# 2_Microcontroler_48.net
KiCad netlist of a schematic drawn in Altium Designer
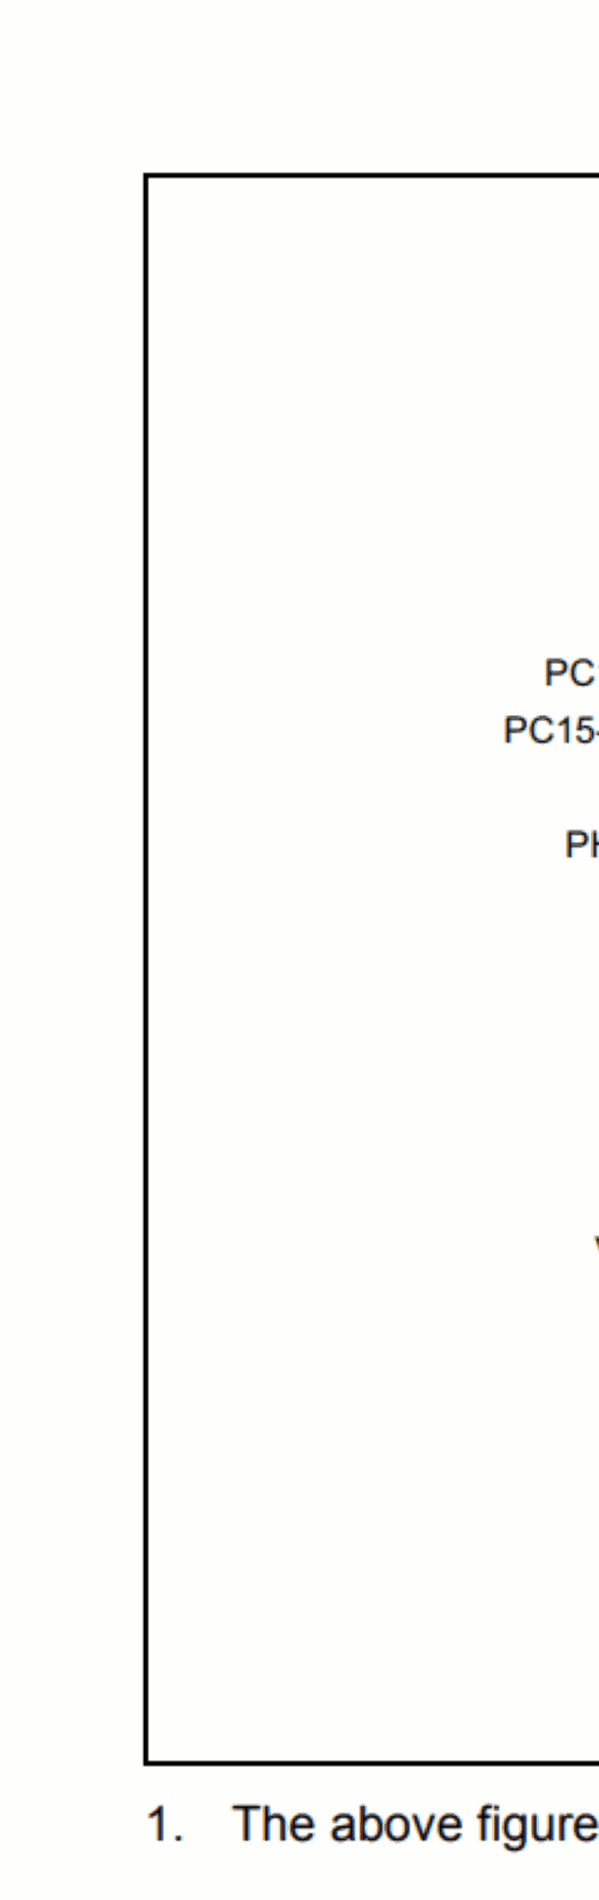
[diagram p0: 2_Microcontroler_48.SchDoc, top left]
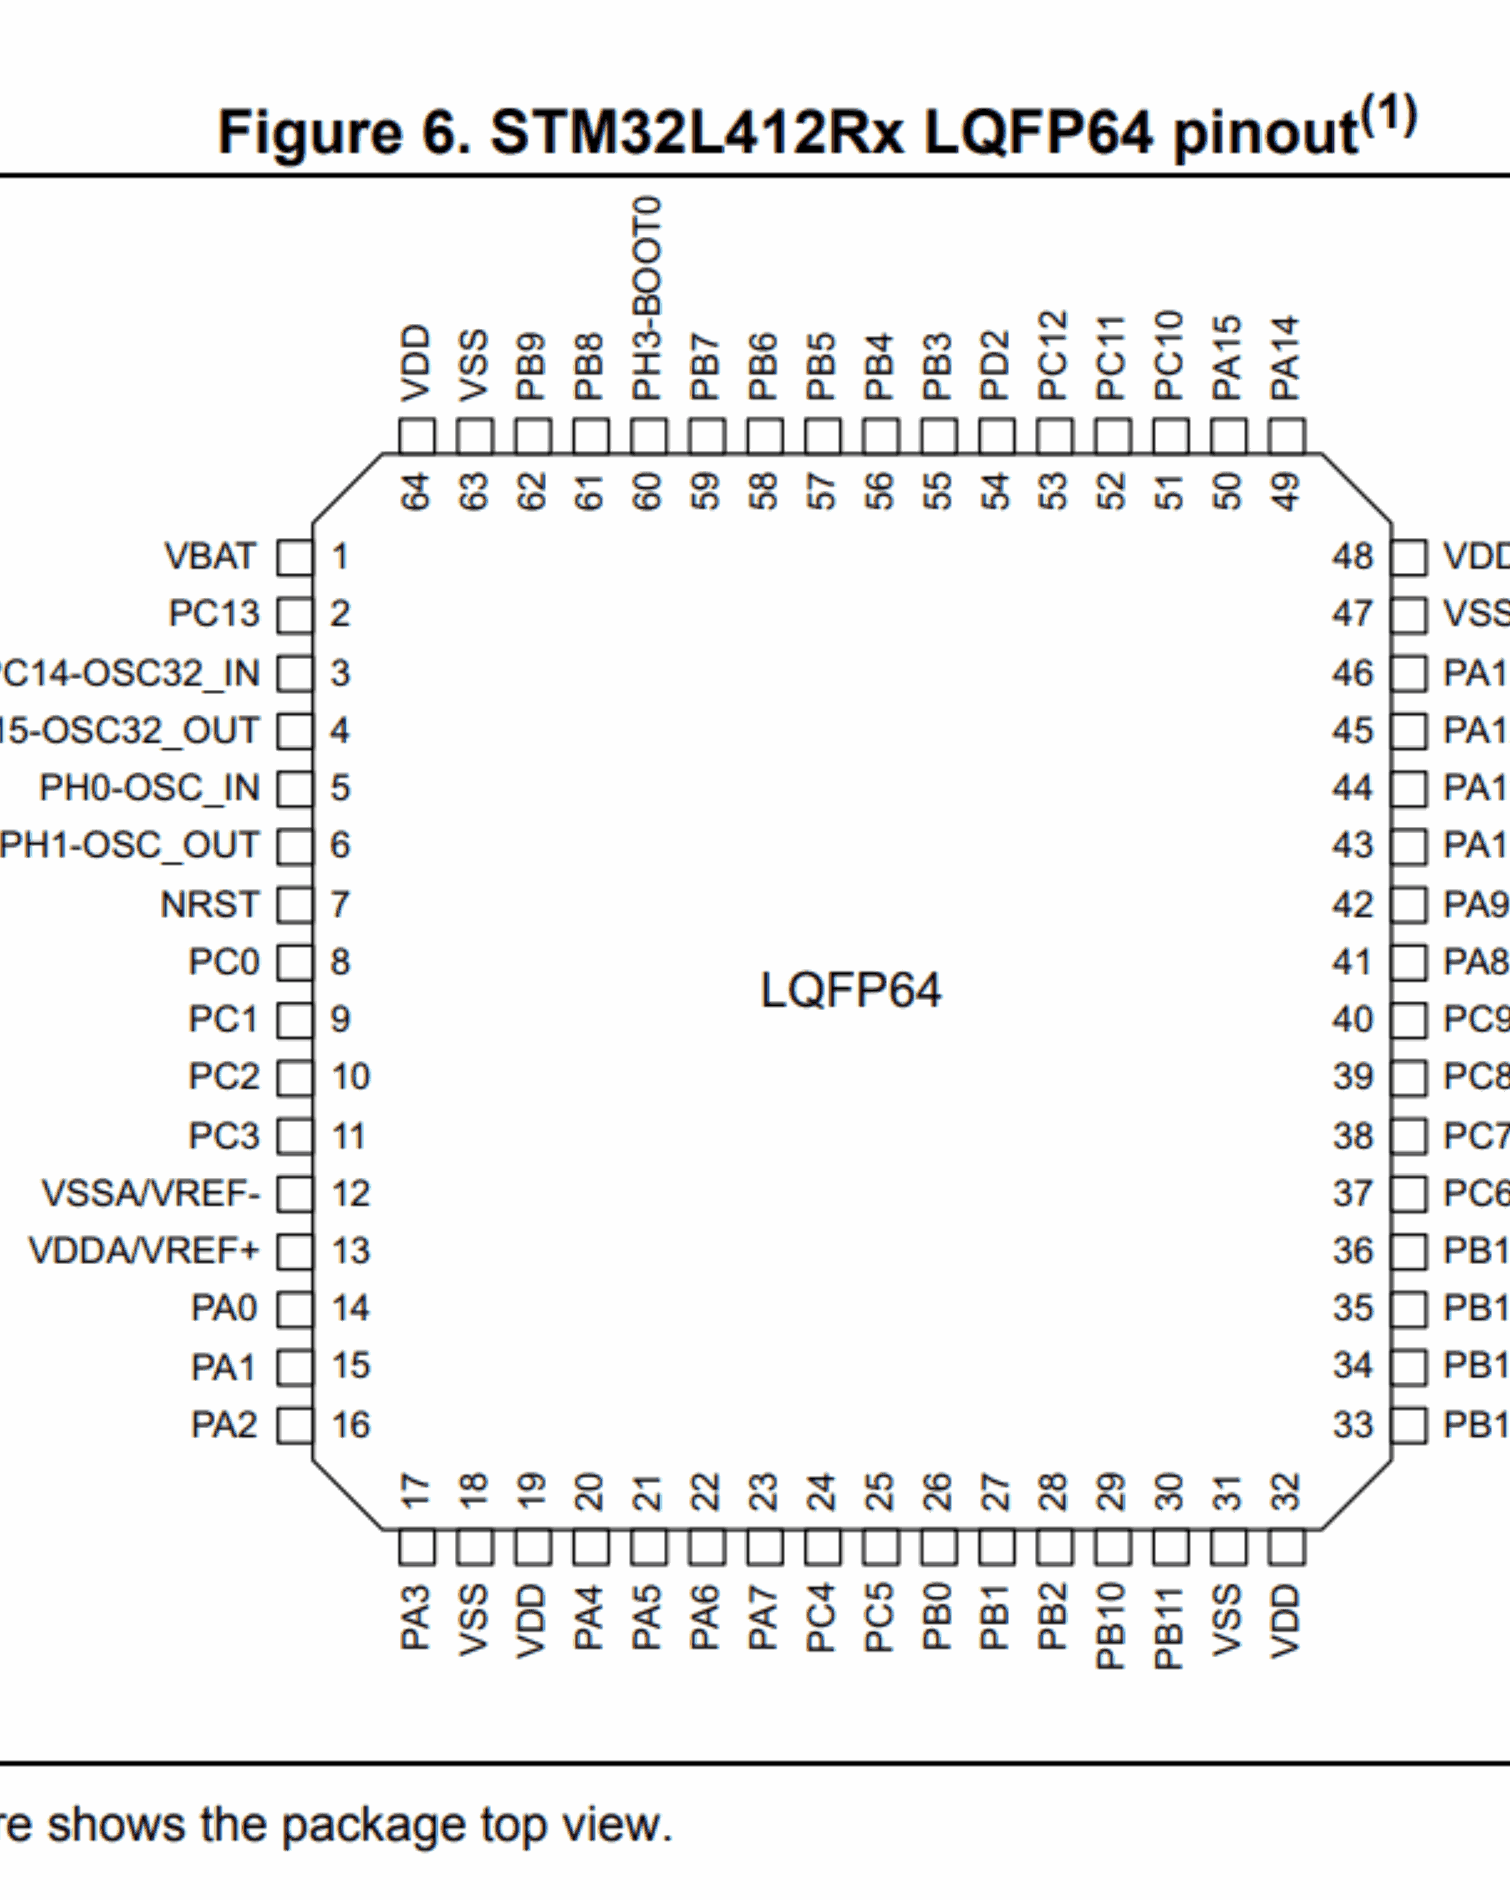
[diagram p1: 2_Microcontroler_48.SchDoc, top middle]
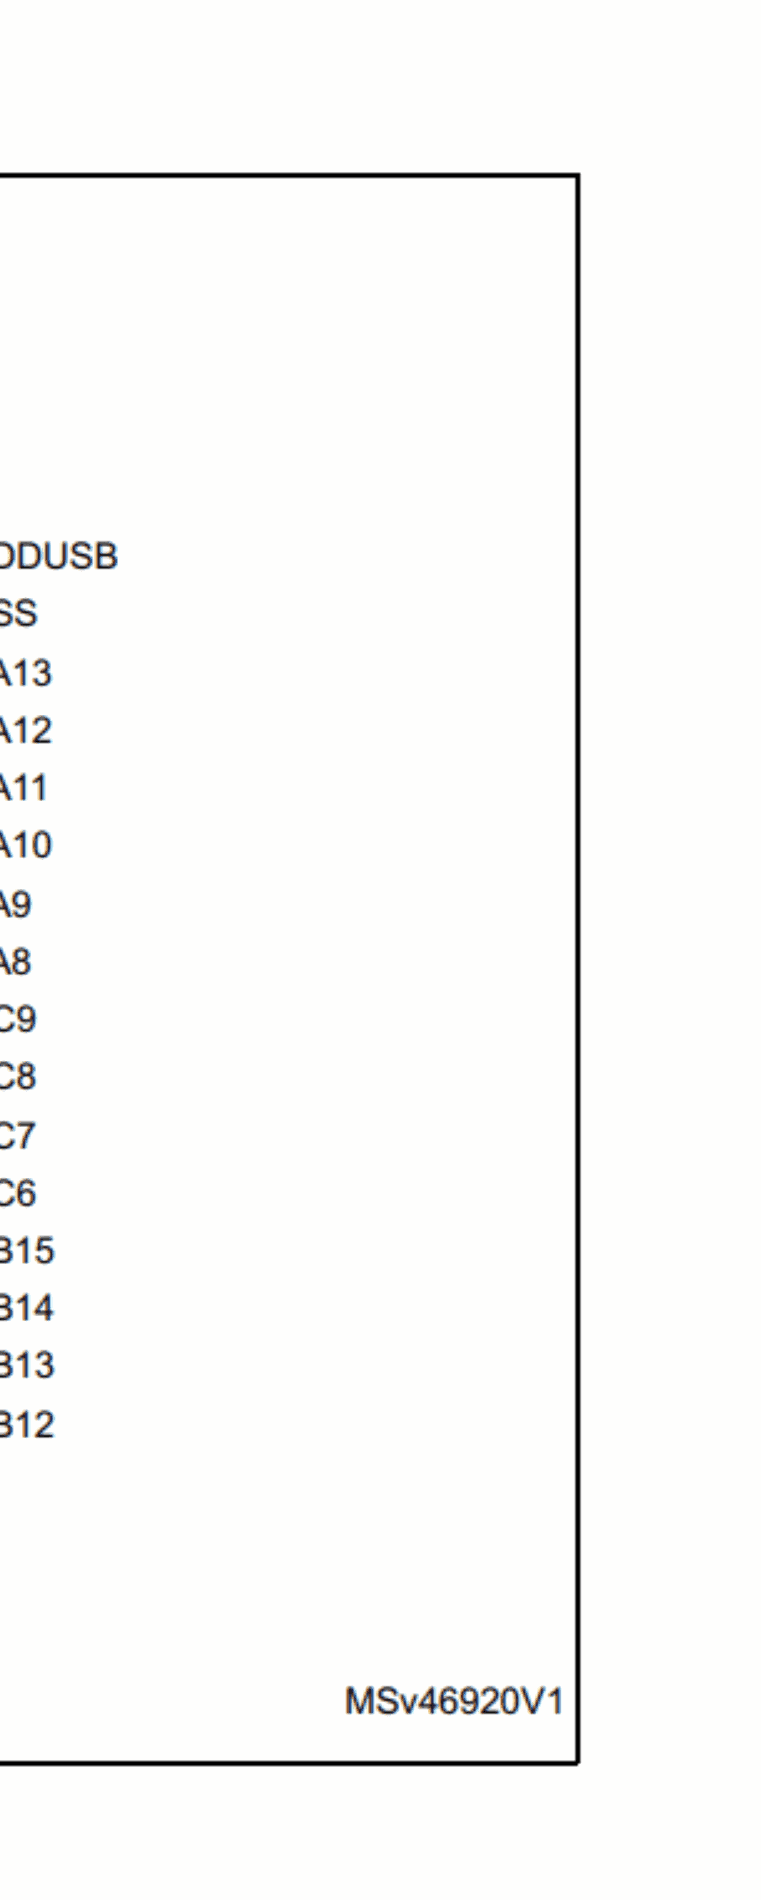
[diagram p2: 2_Microcontroler_48.SchDoc, top right]
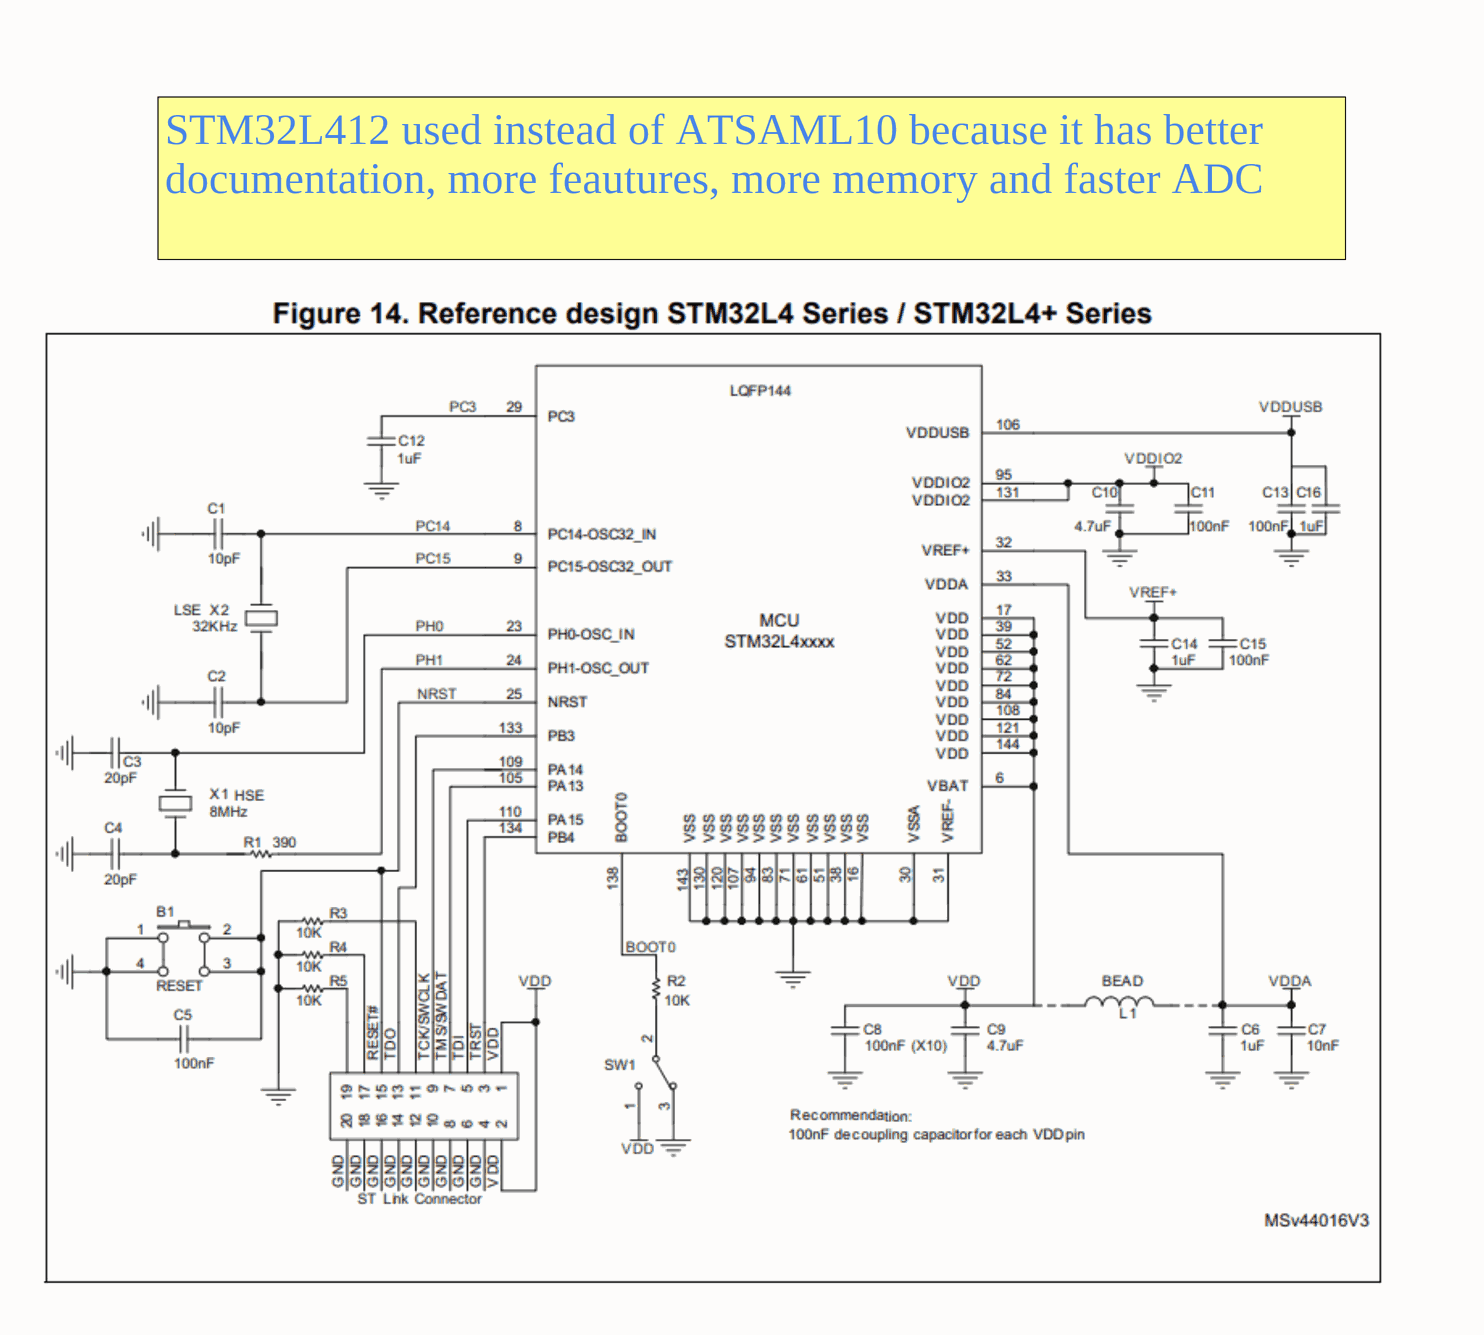
[diagram p3: 2_Microcontroler_48.SchDoc, bottom left]
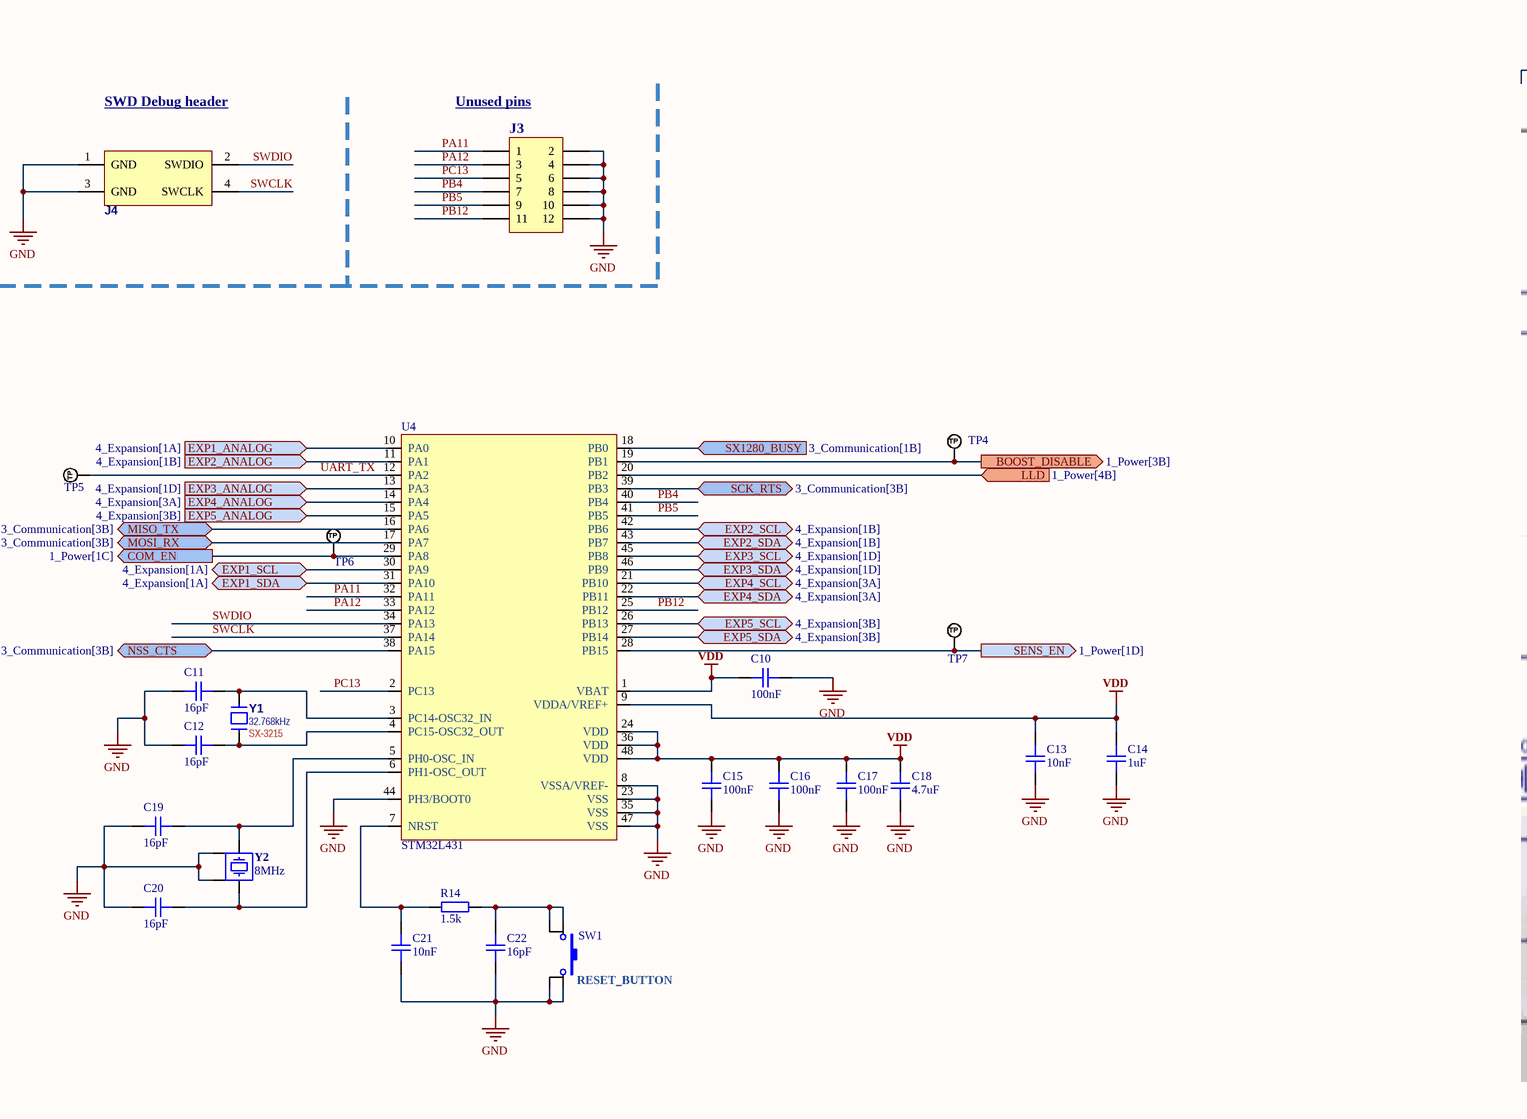
[diagram p4: 2_Microcontroler_48.SchDoc, bottom middle]
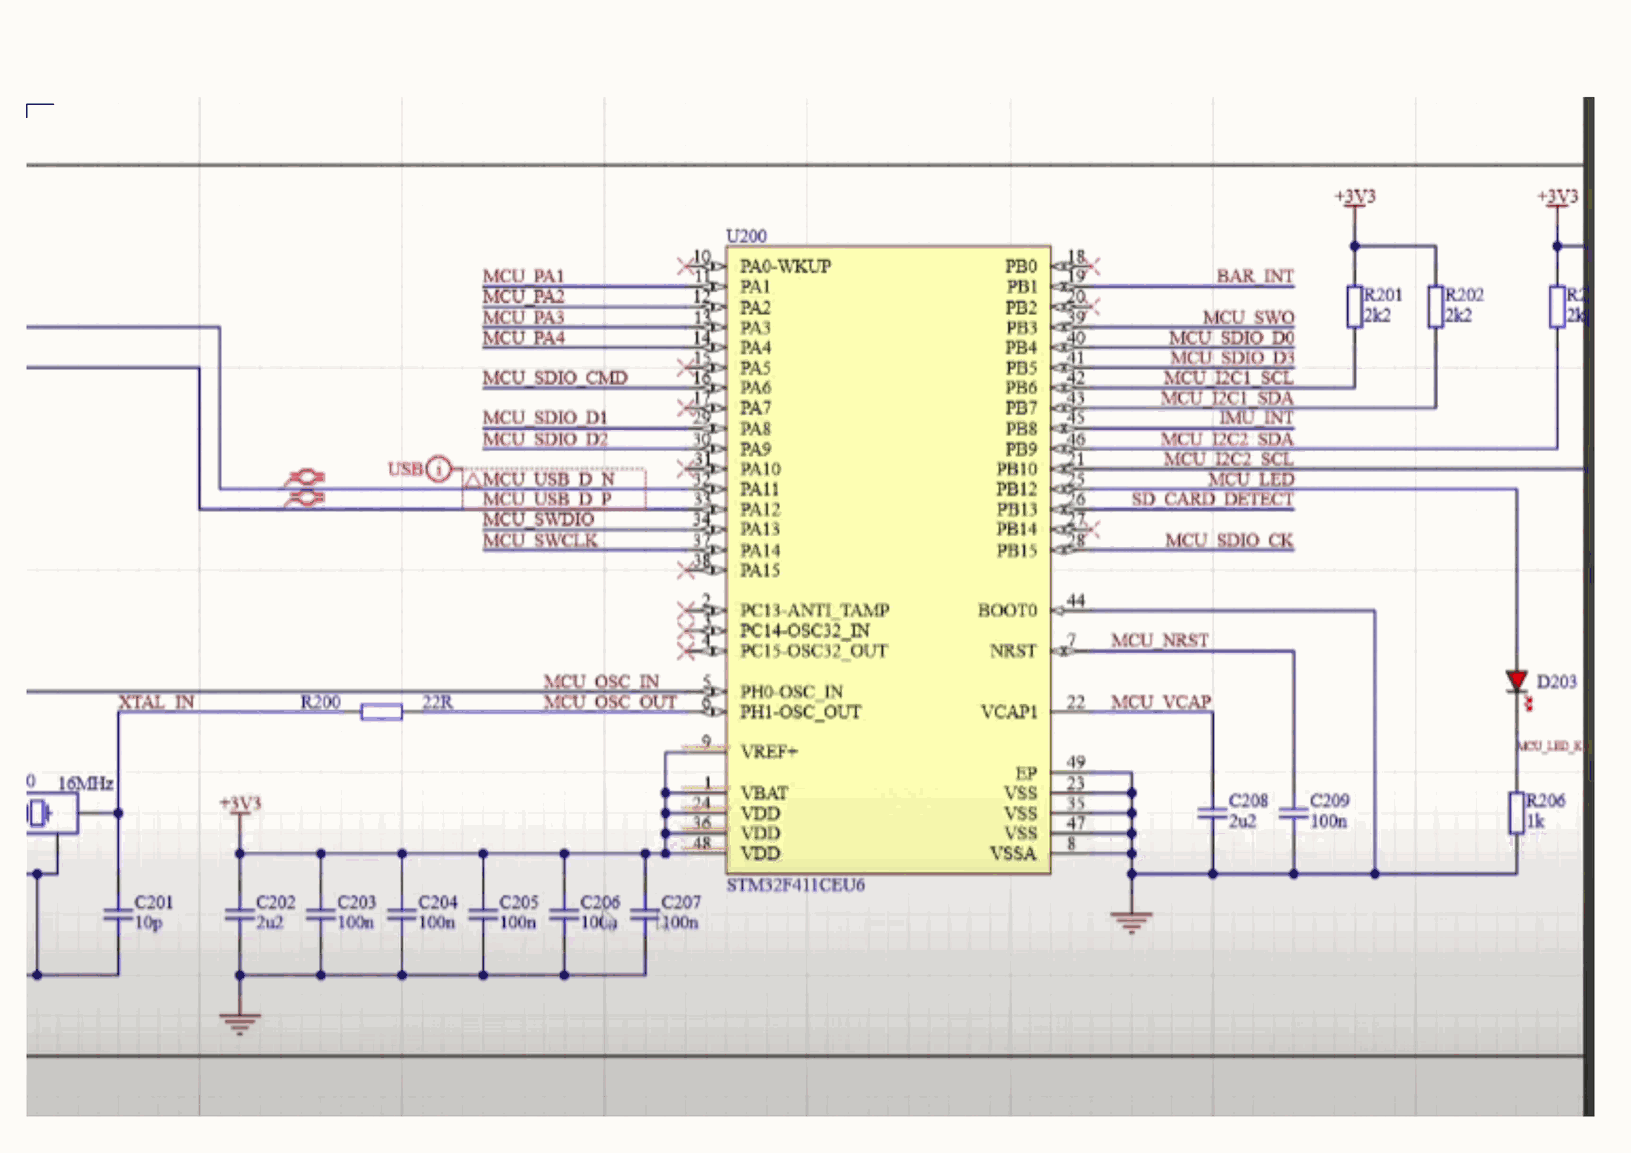
[diagram p5: 2_Microcontroler_48.SchDoc, bottom right]

(export (version "E")
  (design (tool "Eeschema 10.0.6"))
  (components
    (comp (ref "C10")
      (value "100nF")
      (footprint "C0603")
      (description "Capacitor SMD 0603")
      (libsource (lib "Schlib_H2") (part "CAP_0603"))
    )
    (comp (ref "C11")
      (value "16pF")
      (footprint "C0603")
      (description "Capacitor SMD 0603")
      (libsource (lib "Schlib_H2") (part "CAP_0603"))
    )
    (comp (ref "C12")
      (value "16pF")
      (footprint "C0603")
      (description "Capacitor SMD 0603")
      (libsource (lib "Schlib_H2") (part "CAP_0603"))
    )
    (comp (ref "C13")
      (value "10nF")
      (footprint "C0603")
      (description "Capacitor SMD 0603")
      (libsource (lib "Schlib_H2") (part "CAP_0603"))
    )
    (comp (ref "C14")
      (value "1uF")
      (footprint "C0603")
      (description "Capacitor SMD 0603")
      (libsource (lib "Schlib_H2") (part "CAP_0603"))
    )
    (comp (ref "C15")
      (value "100nF")
      (footprint "C0603")
      (description "Capacitor SMD 0603")
      (libsource (lib "Schlib_H2") (part "CAP_0603"))
    )
    (comp (ref "C16")
      (value "100nF")
      (footprint "C0603")
      (description "Capacitor SMD 0603")
      (libsource (lib "Schlib_H2") (part "CAP_0603"))
    )
    (comp (ref "C17")
      (value "100nF")
      (footprint "C0603")
      (description "Capacitor SMD 0603")
      (libsource (lib "Schlib_H2") (part "CAP_0603"))
    )
    (comp (ref "C18")
      (value "4.7uF")
      (footprint "C0603")
      (description "Capacitor SMD 0603")
      (libsource (lib "Schlib_H2") (part "CAP_0603"))
    )
    (comp (ref "C19")
      (value "16pF")
      (footprint "C0603")
      (description "Capacitor SMD 0603")
      (libsource (lib "Schlib_H2") (part "CAP_0603"))
    )
    (comp (ref "C20")
      (value "16pF")
      (footprint "C0603")
      (description "Capacitor SMD 0603")
      (libsource (lib "Schlib_H2") (part "CAP_0603"))
    )
    (comp (ref "C21")
      (value "10nF")
      (footprint "C0603")
      (description "Capacitor SMD 0603")
      (libsource (lib "Schlib_H2") (part "CAP_0603"))
    )
    (comp (ref "C22")
      (value "16pF")
      (footprint "C0603")
      (description "Capacitor SMD 0603")
      (libsource (lib "Schlib_H2") (part "CAP_0603"))
    )
    (comp (ref "J3")
      (value "Header 6X2")
      (footprint "HEADER_6x2_2.54")
      (description "Header, 12-Pin, Dual row")
      (fields (field (name "PUBLISHER") "Altium Limited"))
      (libsource (lib "Schlib_H2") (part "Header 6x2"))
    )
    (comp (ref "J4")
      (value "SWD connector")
      (footprint "HEADER_2x2_2.54")
      (description "Single Wire Debug connector with UART _TX pin")
      (libsource (lib "Schlib_H2") (part "SWD connector"))
    )
    (comp (ref "R14")
      (value "1.5k")
      (footprint "R0603")
      (description "Resistor SMD 0603")
      (libsource (lib "Schlib_H2") (part "RES_0603"))
    )
    (comp (ref "SW1")
      (value "PTS645SM43SMTR92 LFS")
      (footprint "SW_SKRPACE010")
      (description "Switch")
      (fields (field (name "PUBLISHER") "Altium Limited"))
      (libsource (lib "Schlib_H2") (part "SW-PB"))
    )
    (comp (ref "TP4")
      (value "TP_NOBOM")
      (footprint "TEST_PAD_THD")
      (description "Test Point Round 1mm (NO BOM)")
      (libsource (lib "Schlib_H2") (part "TEST_POINT_RND_1MM"))
    )
    (comp (ref "TP5")
      (value "TP_NOBOM")
      (footprint "TEST_PAD_THD")
      (description "Test Point Round 1mm (NO BOM)")
      (libsource (lib "Schlib_H2") (part "TEST_POINT_RND_1MM"))
    )
    (comp (ref "TP6")
      (value "TP_NOBOM")
      (footprint "TEST_PAD_THD")
      (description "Test Point Round 1mm (NO BOM)")
      (libsource (lib "Schlib_H2") (part "TEST_POINT_RND_1MM"))
    )
    (comp (ref "TP7")
      (value "TP_NOBOM")
      (footprint "TEST_PAD_THD")
      (description "Test Point Round 1mm (NO BOM)")
      (libsource (lib "Schlib_H2") (part "TEST_POINT_RND_1MM"))
    )
    (comp (ref "U4")
      (value "STM32L431")
      (footprint "QFPN-48")
      (description "Ultra-low-power Arm® Cortex®-M4 32-bit MCU+FPU, 100DMIPS,\r\n up to 128KB flash, 40KB SRAM(LQFP48)")
      (libsource (lib "Schlib_H2") (part "STM32L431"))
    )
    (comp (ref "Y1")
      (value "32.768kHz")
      (footprint "CRYSTAL_SX-3215")
      (description "Crystal")
      (fields (field (name "PACKAGEREFERENCE") "SX-3215"))
      (libsource (lib "Schlib_H2") (part "CRYSTAL_1"))
    )
    (comp (ref "Y2")
      (value "8MHz")
      (footprint "CRYSTAL_ECX-32_3.2x2.5x0.8 - duplicate")
      (description "Crystal")
      (fields
        (field (name "MANUFACTURER") "Epson")
        (field (name "MANUFACTURER PART NUMBER") "TSX-3225 24.0000MF15X-AC")
      )
      (libsource (lib "Schlib_H2") (part "Crystal"))
    )
  )
  (nets
    (net (code "1") (name "/BOOST_DISABLE") (class "Default")
      (node (ref "TP4") (pin "1") (pinfunction "TP_1") (pintype "passive"))
      (node (ref "U4") (pin "19") (pinfunction "PB1_19") (pintype "passive"))
    )
    (net (code "2") (name "/COM_EN") (class "Default")
      (node (ref "TP6") (pin "1") (pinfunction "TP_1") (pintype "passive"))
      (node (ref "U4") (pin "29") (pinfunction "PA8_29") (pintype "passive"))
    )
    (net (code "3") (name "/EXP1_ANALOG") (class "Default")
      (node (ref "U4") (pin "10") (pinfunction "PA0_10") (pintype "passive"))
    )
    (net (code "4") (name "/EXP1_SCL") (class "Default")
      (node (ref "U4") (pin "30") (pinfunction "PA9_30") (pintype "passive"))
    )
    (net (code "5") (name "/EXP1_SDA") (class "Default")
      (node (ref "U4") (pin "31") (pinfunction "PA10_31") (pintype "passive"))
    )
    (net (code "6") (name "/EXP2_ANALOG") (class "Default")
      (node (ref "U4") (pin "11") (pinfunction "PA1_11") (pintype "passive"))
    )
    (net (code "7") (name "/EXP2_SCL") (class "Default")
      (node (ref "U4") (pin "42") (pinfunction "PB6_42") (pintype "passive"))
    )
    (net (code "8") (name "/EXP2_SDA") (class "Default")
      (node (ref "U4") (pin "43") (pinfunction "PB7_43") (pintype "passive"))
    )
    (net (code "9") (name "/EXP3_ANALOG") (class "Default")
      (node (ref "U4") (pin "13") (pinfunction "PA3_13") (pintype "passive"))
    )
    (net (code "10") (name "/EXP3_SCL") (class "Default")
      (node (ref "U4") (pin "45") (pinfunction "PB8_45") (pintype "passive"))
    )
    (net (code "11") (name "/EXP3_SDA") (class "Default")
      (node (ref "U4") (pin "46") (pinfunction "PB9_46") (pintype "passive"))
    )
    (net (code "12") (name "/EXP4_ANALOG") (class "Default")
      (node (ref "U4") (pin "14") (pinfunction "PA4_14") (pintype "passive"))
    )
    (net (code "13") (name "/EXP4_SCL") (class "Default")
      (node (ref "U4") (pin "21") (pinfunction "PB10_21") (pintype "passive"))
    )
    (net (code "14") (name "/EXP4_SDA") (class "Default")
      (node (ref "U4") (pin "22") (pinfunction "PB11_22") (pintype "passive"))
    )
    (net (code "15") (name "/EXP5_ANALOG") (class "Default")
      (node (ref "U4") (pin "15") (pinfunction "PA5_15") (pintype "passive"))
    )
    (net (code "16") (name "/EXP5_SCL") (class "Default")
      (node (ref "U4") (pin "26") (pinfunction "PB13_26") (pintype "passive"))
    )
    (net (code "17") (name "/EXP5_SDA") (class "Default")
      (node (ref "U4") (pin "27") (pinfunction "PB14_27") (pintype "passive"))
    )
    (net (code "18") (name "/LLD") (class "Default")
      (node (ref "U4") (pin "20") (pinfunction "PB2_20") (pintype "passive"))
    )
    (net (code "19") (name "/MISO_TX") (class "Default")
      (node (ref "U4") (pin "16") (pinfunction "PA6_16") (pintype "passive"))
    )
    (net (code "20") (name "/MOSI_RX") (class "Default")
      (node (ref "U4") (pin "17") (pinfunction "PA7_17") (pintype "passive"))
    )
    (net (code "21") (name "/NSS_CTS") (class "Default")
      (node (ref "U4") (pin "38") (pinfunction "PA15_38") (pintype "passive"))
    )
    (net (code "22") (name "/PA11") (class "Default")
      (node (ref "J3") (pin "1") (pinfunction "1_1") (pintype "passive"))
      (node (ref "U4") (pin "32") (pinfunction "PA11_32") (pintype "passive"))
    )
    (net (code "23") (name "/PA12") (class "Default")
      (node (ref "J3") (pin "3") (pinfunction "3_3") (pintype "passive"))
      (node (ref "U4") (pin "33") (pinfunction "PA12_33") (pintype "passive"))
    )
    (net (code "24") (name "/PB4") (class "Default")
      (node (ref "J3") (pin "7") (pinfunction "7_7") (pintype "passive"))
      (node (ref "U4") (pin "40") (pinfunction "PB4_40") (pintype "passive"))
    )
    (net (code "25") (name "/PB5") (class "Default")
      (node (ref "J3") (pin "9") (pinfunction "9_9") (pintype "passive"))
      (node (ref "U4") (pin "41") (pinfunction "PB5_41") (pintype "passive"))
    )
    (net (code "26") (name "/PB12") (class "Default")
      (node (ref "J3") (pin "11") (pinfunction "11_11") (pintype "passive"))
      (node (ref "U4") (pin "25") (pinfunction "PB12_25") (pintype "passive"))
    )
    (net (code "27") (name "/PC13") (class "Default")
      (node (ref "J3") (pin "5") (pinfunction "5_5") (pintype "passive"))
      (node (ref "U4") (pin "2") (pinfunction "PC13_2") (pintype "passive"))
    )
    (net (code "28") (name "/SCK_RTS") (class "Default")
      (node (ref "U4") (pin "39") (pinfunction "PB3_39") (pintype "passive"))
    )
    (net (code "29") (name "/SENS_EN") (class "Default")
      (node (ref "TP7") (pin "1") (pinfunction "TP_1") (pintype "passive"))
      (node (ref "U4") (pin "28") (pinfunction "PB15_28") (pintype "passive"))
    )
    (net (code "30") (name "/SWCLK") (class "Default")
      (node (ref "J4") (pin "4") (pinfunction "SWCLK_4") (pintype "passive"))
      (node (ref "U4") (pin "37") (pinfunction "PA14_37") (pintype "passive"))
    )
    (net (code "31") (name "/SWDIO") (class "Default")
      (node (ref "J4") (pin "2") (pinfunction "SWDIO_2") (pintype "passive"))
      (node (ref "U4") (pin "34") (pinfunction "PA13_34") (pintype "passive"))
    )
    (net (code "32") (name "/SX1280_BUSY") (class "Default")
      (node (ref "U4") (pin "18") (pinfunction "PB0_18") (pintype "passive"))
    )
    (net (code "33") (name "/UART_TX") (class "Default")
      (node (ref "TP5") (pin "1") (pinfunction "TP_1") (pintype "passive"))
      (node (ref "U4") (pin "12") (pinfunction "PA2_12") (pintype "passive"))
    )
    (net (code "34") (name "GND") (class "Default")
      (node (ref "C10") (pin "1") (pinfunction "1_1") (pintype "passive"))
      (node (ref "C11") (pin "1") (pinfunction "1_1") (pintype "passive"))
      (node (ref "C12") (pin "1") (pinfunction "1_1") (pintype "passive"))
      (node (ref "C13") (pin "1") (pinfunction "1_1") (pintype "passive"))
      (node (ref "C14") (pin "1") (pinfunction "1_1") (pintype "passive"))
      (node (ref "C15") (pin "1") (pinfunction "1_1") (pintype "passive"))
      (node (ref "C16") (pin "1") (pinfunction "1_1") (pintype "passive"))
      (node (ref "C17") (pin "1") (pinfunction "1_1") (pintype "passive"))
      (node (ref "C18") (pin "1") (pinfunction "1_1") (pintype "passive"))
      (node (ref "C19") (pin "1") (pinfunction "1_1") (pintype "passive"))
      (node (ref "C20") (pin "1") (pinfunction "1_1") (pintype "passive"))
      (node (ref "C21") (pin "1") (pinfunction "1_1") (pintype "passive"))
      (node (ref "C22") (pin "1") (pinfunction "1_1") (pintype "passive"))
      (node (ref "J3") (pin "10") (pinfunction "10_10") (pintype "passive"))
      (node (ref "J3") (pin "12") (pinfunction "12_12") (pintype "passive"))
      (node (ref "J3") (pin "2") (pinfunction "2_2") (pintype "passive"))
      (node (ref "J3") (pin "4") (pinfunction "4_4") (pintype "passive"))
      (node (ref "J3") (pin "6") (pinfunction "6_6") (pintype "passive"))
      (node (ref "J3") (pin "8") (pinfunction "8_8") (pintype "passive"))
      (node (ref "J4") (pin "1") (pinfunction "GND_1") (pintype "passive"))
      (node (ref "J4") (pin "3") (pinfunction "GND_3") (pintype "passive"))
      (node (ref "SW1") (pin "3") (pinfunction "3_3") (pintype "passive"))
      (node (ref "SW1") (pin "4") (pinfunction "4_4") (pintype "passive"))
      (node (ref "U4") (pin "23") (pinfunction "VSS_23") (pintype "passive"))
      (node (ref "U4") (pin "35") (pinfunction "VSS_35") (pintype "passive"))
      (node (ref "U4") (pin "44") (pinfunction "PH3/BOOT0_44") (pintype "passive"))
      (node (ref "U4") (pin "47") (pinfunction "VSS_47") (pintype "passive"))
      (node (ref "U4") (pin "8") (pinfunction "VSSA/VREF-_8") (pintype "passive"))
      (node (ref "Y2") (pin "2") (pinfunction "2_2") (pintype "passive"))
      (node (ref "Y2") (pin "4") (pinfunction "4_4") (pintype "passive"))
    )
    (net (code "35") (name "Net-(C22-Pad2)") (class "Default")
      (node (ref "C22") (pin "2") (pinfunction "2_2") (pintype "passive"))
      (node (ref "R14") (pin "2") (pinfunction "2_2") (pintype "passive"))
      (node (ref "SW1") (pin "1") (pinfunction "1_1") (pintype "passive"))
      (node (ref "SW1") (pin "2") (pinfunction "2_2") (pintype "passive"))
    )
    (net (code "36") (name "Net-(U4-NRST)") (class "Default")
      (node (ref "C21") (pin "2") (pinfunction "2_2") (pintype "passive"))
      (node (ref "R14") (pin "1") (pinfunction "1_1") (pintype "passive"))
      (node (ref "U4") (pin "7") (pinfunction "NRST_7") (pintype "passive"))
    )
    (net (code "37") (name "Net-(U4-PC14-OSC32_IN)") (class "Default")
      (node (ref "C11") (pin "2") (pinfunction "2_2") (pintype "passive"))
      (node (ref "U4") (pin "3") (pinfunction "PC14-OSC32_IN_3") (pintype "passive"))
      (node (ref "Y1") (pin "2") (pinfunction "2_2") (pintype "passive"))
    )
    (net (code "38") (name "Net-(U4-PC15-OSC32_OUT)") (class "Default")
      (node (ref "C12") (pin "2") (pinfunction "2_2") (pintype "passive"))
      (node (ref "U4") (pin "4") (pinfunction "PC15-OSC32_OUT_4") (pintype "passive"))
      (node (ref "Y1") (pin "1") (pinfunction "1_1") (pintype "passive"))
    )
    (net (code "39") (name "Net-(U4-PH0-OSC_IN)") (class "Default")
      (node (ref "C19") (pin "2") (pinfunction "2_2") (pintype "passive"))
      (node (ref "U4") (pin "5") (pinfunction "PH0-OSC_IN_5") (pintype "passive"))
      (node (ref "Y2") (pin "3") (pinfunction "3_3") (pintype "passive"))
    )
    (net (code "40") (name "Net-(U4-PH1-OSC_OUT)") (class "Default")
      (node (ref "C20") (pin "2") (pinfunction "2_2") (pintype "passive"))
      (node (ref "U4") (pin "6") (pinfunction "PH1-OSC_OUT_6") (pintype "passive"))
      (node (ref "Y2") (pin "1") (pinfunction "1_1") (pintype "passive"))
    )
    (net (code "41") (name "VDD") (class "Default")
      (node (ref "C10") (pin "2") (pinfunction "2_2") (pintype "passive"))
      (node (ref "C13") (pin "2") (pinfunction "2_2") (pintype "passive"))
      (node (ref "C14") (pin "2") (pinfunction "2_2") (pintype "passive"))
      (node (ref "C15") (pin "2") (pinfunction "2_2") (pintype "passive"))
      (node (ref "C16") (pin "2") (pinfunction "2_2") (pintype "passive"))
      (node (ref "C17") (pin "2") (pinfunction "2_2") (pintype "passive"))
      (node (ref "C18") (pin "2") (pinfunction "2_2") (pintype "passive"))
      (node (ref "U4") (pin "1") (pinfunction "VBAT_1") (pintype "passive"))
      (node (ref "U4") (pin "24") (pinfunction "VDD_24") (pintype "passive"))
      (node (ref "U4") (pin "36") (pinfunction "VDD_36") (pintype "passive"))
      (node (ref "U4") (pin "48") (pinfunction "VDD_48") (pintype "passive"))
      (node (ref "U4") (pin "9") (pinfunction "VDDA/VREF+_9") (pintype "passive"))
    )
  )
)
